# MCU_Module.net
KiCad netlist of a schematic drawn in Altium Designer
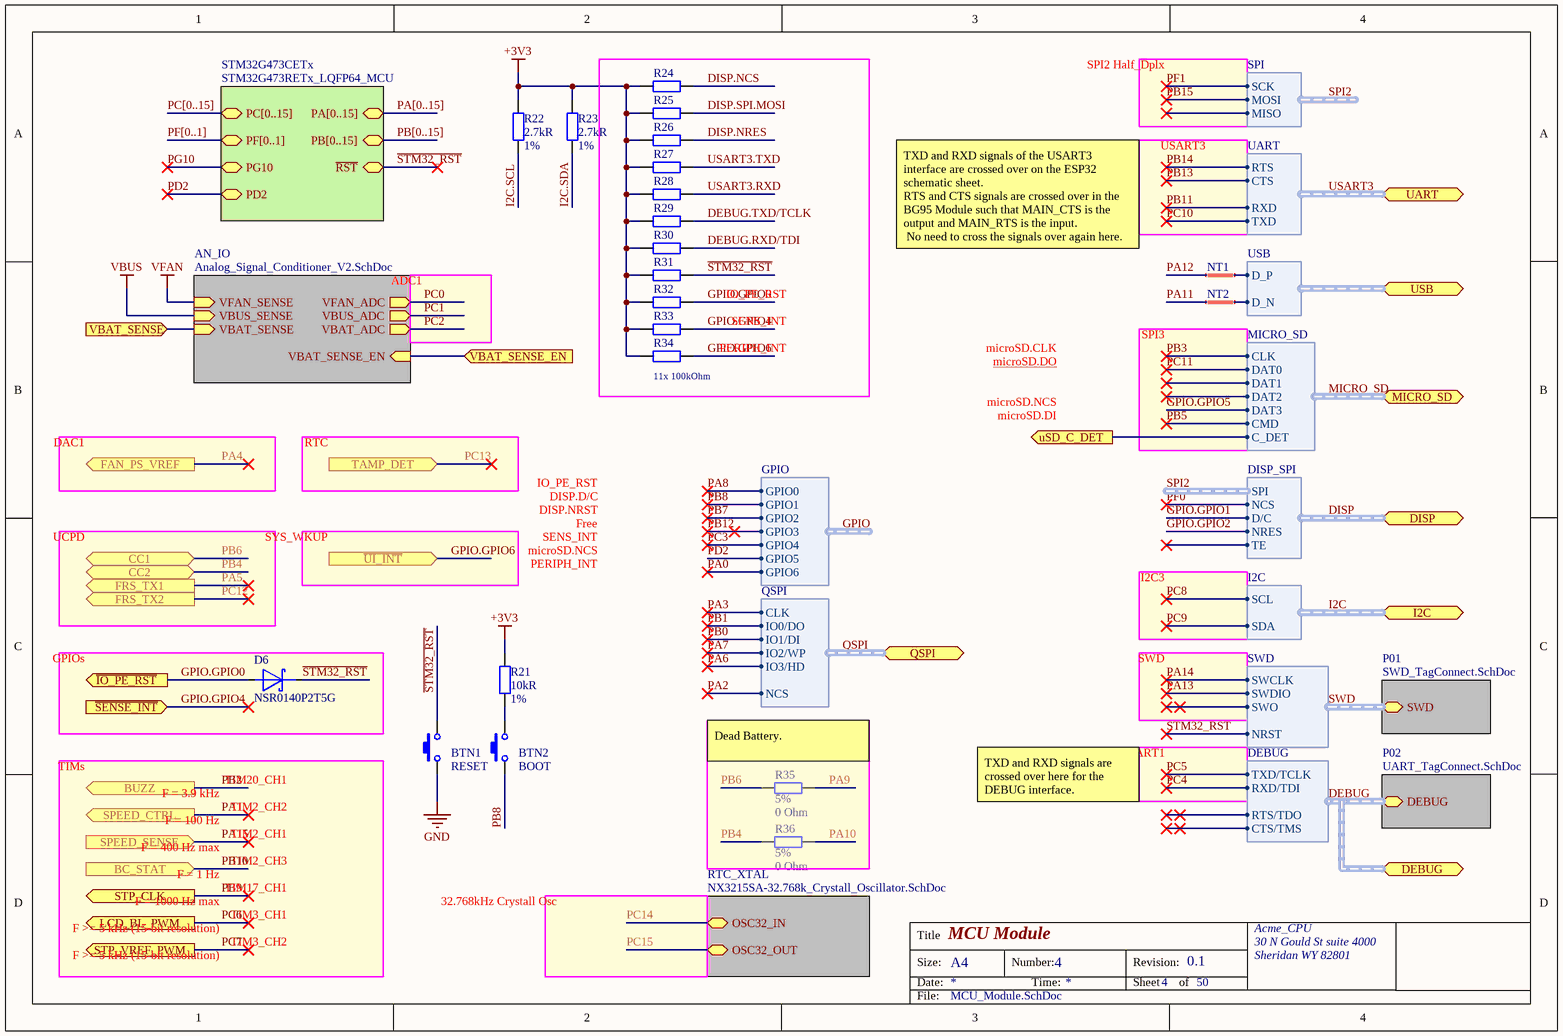
[diagram p0: MCU_Module.SchDoc]

(export (version "E")
  (design (tool "Eeschema 10.0.6"))
  (components
    (comp (ref "BTN1")
      (value "RESET")
      (footprint "SWITCH USLPT2819DT2TR TACTILE TE")
      (description "Tactile Switch SPST-NO Top Actuated Surface Mount")
      (fields
        (field (name "MANUFACTURER") "TE Connectivity")
        (field (name "MANUFACTURER PART NUMBER") "USLPT2819DT2TR")
      )
      (libsource (lib "BLDC_Motor_Driver") (part "TACT ULTRA TB 2.8X1.9X0.6 160GF"))
    )
    (comp (ref "BTN2")
      (value "BOOT")
      (footprint "SWITCH USLPT2819DT2TR TACTILE TE")
      (description "Tactile Switch SPST-NO Top Actuated Surface Mount")
      (fields
        (field (name "MANUFACTURER") "TE Connectivity")
        (field (name "MANUFACTURER PART NUMBER") "USLPT2819DT2TR")
      )
      (libsource (lib "BLDC_Motor_Driver") (part "TACT ULTRA TB 2.8X1.9X0.6 160GF"))
    )
    (comp (ref "D6")
      (value "NSR0140P2T5G")
      (footprint "SODFL100X40-2N")
      (description "Diode Schottky 30V 70mA (DC) Surface Mount SOD-923")
      (fields (field (name "MANUFACTURER") "ON Semiconductor"))
      (libsource (lib "diodes_schottky") (part "DIODE SCHOTTKY 30V 70MA SOD923"))
    )
    (comp (ref "NT1")
      (value "Net Tie")
      (footprint "Net Tie 6x30mil")
      (libsource (lib "BLDC_Motor_Driver") (part "Net Tie Line"))
    )
    (comp (ref "NT2")
      (value "Net Tie")
      (footprint "Net Tie 6x30mil")
      (libsource (lib "BLDC_Motor_Driver") (part "Net Tie Line"))
    )
    (comp (ref "R21")
      (value "RES SMD 10K OHM 1% 1/16W 0402")
      (footprint "R0402")
      (description "10 kOhms ±1% 0.063W, 1/16W Chip Resistor 0402 (1005 Metric) Moisture Resistant Thick Film")
      (fields
        (field (name "MANUFACTURER PART NUMBER") "RC0402FR-0710KP")
        (field (name "MANUFACTURER") "Yageo")
        (field (name "RESISTANCE") "10kR")
        (field (name "TOLERANCE") "1%")
      )
      (libsource (lib "resistors_smd") (part "RES SMD 10K OHM 1% 1/16W 0402"))
    )
    (comp (ref "R22")
      (value "RES SMD 2.7K OHM 1% 1/16W 0402")
      (footprint "R0402")
      (description "2.7 kOhms ±1% 0.063W, 1/16W Chip Resistor 0402 (1005 Metric) Moisture Resistant Thick Film")
      (fields
        (field (name "MANUFACTURER") "Yageo")
        (field (name "MANUFACTURER PART NUMBER") "RC0402FR-072K7L")
        (field (name "RESISTANCE") "2.7kR")
        (field (name "TOLERANCE") "1%")
      )
      (libsource (lib "resistors_smd") (part "RES SMD 2.7K OHM 1% 1/16W 0402"))
    )
    (comp (ref "R23")
      (value "RES SMD 2.7K OHM 1% 1/16W 0402")
      (footprint "R0402")
      (description "2.7 kOhms ±1% 0.063W, 1/16W Chip Resistor 0402 (1005 Metric) Moisture Resistant Thick Film")
      (fields
        (field (name "MANUFACTURER") "Yageo")
        (field (name "MANUFACTURER PART NUMBER") "RC0402FR-072K7L")
        (field (name "RESISTANCE") "2.7kR")
        (field (name "TOLERANCE") "1%")
      )
      (libsource (lib "resistors_smd") (part "RES SMD 2.7K OHM 1% 1/16W 0402"))
    )
    (comp (ref "R24")
      (value "RES SMD 100K OHM 1% 1/16W 0402")
      (footprint "R0402")
      (description "100 kOhms ±1% 0.063W, 1/16W Chip Resistor 0402 (1005 Metric) Moisture Resistant Thick Film")
      (fields
        (field (name "MANUFACTURER") "Yageo")
        (field (name "MANUFACTURER PART NUMBER") "RC0402FR-07100KL")
      )
      (libsource (lib "resistors_smd") (part "RES SMD 100K OHM 1% 1/16W 0402"))
    )
    (comp (ref "R25")
      (value "RES SMD 100K OHM 1% 1/16W 0402")
      (footprint "R0402")
      (description "100 kOhms ±1% 0.063W, 1/16W Chip Resistor 0402 (1005 Metric) Moisture Resistant Thick Film")
      (fields
        (field (name "MANUFACTURER") "Yageo")
        (field (name "MANUFACTURER PART NUMBER") "RC0402FR-07100KL")
      )
      (libsource (lib "resistors_smd") (part "RES SMD 100K OHM 1% 1/16W 0402"))
    )
    (comp (ref "R26")
      (value "RES SMD 100K OHM 1% 1/16W 0402")
      (footprint "R0402")
      (description "100 kOhms ±1% 0.063W, 1/16W Chip Resistor 0402 (1005 Metric) Moisture Resistant Thick Film")
      (fields
        (field (name "MANUFACTURER") "Yageo")
        (field (name "MANUFACTURER PART NUMBER") "RC0402FR-07100KL")
      )
      (libsource (lib "resistors_smd") (part "RES SMD 100K OHM 1% 1/16W 0402"))
    )
    (comp (ref "R27")
      (value "RES SMD 100K OHM 1% 1/16W 0402")
      (footprint "R0402")
      (description "100 kOhms ±1% 0.063W, 1/16W Chip Resistor 0402 (1005 Metric) Moisture Resistant Thick Film")
      (fields
        (field (name "MANUFACTURER") "Yageo")
        (field (name "MANUFACTURER PART NUMBER") "RC0402FR-07100KL")
      )
      (libsource (lib "resistors_smd") (part "RES SMD 100K OHM 1% 1/16W 0402"))
    )
    (comp (ref "R28")
      (value "RES SMD 100K OHM 1% 1/16W 0402")
      (footprint "R0402")
      (description "100 kOhms ±1% 0.063W, 1/16W Chip Resistor 0402 (1005 Metric) Moisture Resistant Thick Film")
      (fields
        (field (name "MANUFACTURER") "Yageo")
        (field (name "MANUFACTURER PART NUMBER") "RC0402FR-07100KL")
      )
      (libsource (lib "resistors_smd") (part "RES SMD 100K OHM 1% 1/16W 0402"))
    )
    (comp (ref "R29")
      (value "RES SMD 100K OHM 1% 1/16W 0402")
      (footprint "R0402")
      (description "100 kOhms ±1% 0.063W, 1/16W Chip Resistor 0402 (1005 Metric) Moisture Resistant Thick Film")
      (fields
        (field (name "MANUFACTURER") "Yageo")
        (field (name "MANUFACTURER PART NUMBER") "RC0402FR-07100KL")
      )
      (libsource (lib "resistors_smd") (part "RES SMD 100K OHM 1% 1/16W 0402"))
    )
    (comp (ref "R30")
      (value "RES SMD 100K OHM 1% 1/16W 0402")
      (footprint "R0402")
      (description "100 kOhms ±1% 0.063W, 1/16W Chip Resistor 0402 (1005 Metric) Moisture Resistant Thick Film")
      (fields
        (field (name "MANUFACTURER") "Yageo")
        (field (name "MANUFACTURER PART NUMBER") "RC0402FR-07100KL")
      )
      (libsource (lib "resistors_smd") (part "RES SMD 100K OHM 1% 1/16W 0402"))
    )
    (comp (ref "R31")
      (value "RES SMD 100K OHM 1% 1/16W 0402")
      (footprint "R0402")
      (description "100 kOhms ±1% 0.063W, 1/16W Chip Resistor 0402 (1005 Metric) Moisture Resistant Thick Film")
      (fields
        (field (name "MANUFACTURER") "Yageo")
        (field (name "MANUFACTURER PART NUMBER") "RC0402FR-07100KL")
      )
      (libsource (lib "resistors_smd") (part "RES SMD 100K OHM 1% 1/16W 0402"))
    )
    (comp (ref "R32")
      (value "RES SMD 100K OHM 1% 1/16W 0402")
      (footprint "R0402")
      (description "100 kOhms ±1% 0.063W, 1/16W Chip Resistor 0402 (1005 Metric) Moisture Resistant Thick Film")
      (fields
        (field (name "MANUFACTURER") "Yageo")
        (field (name "MANUFACTURER PART NUMBER") "RC0402FR-07100KL")
      )
      (libsource (lib "resistors_smd") (part "RES SMD 100K OHM 1% 1/16W 0402"))
    )
    (comp (ref "R33")
      (value "RES SMD 100K OHM 1% 1/16W 0402")
      (footprint "R0402")
      (description "100 kOhms ±1% 0.063W, 1/16W Chip Resistor 0402 (1005 Metric) Moisture Resistant Thick Film")
      (fields
        (field (name "MANUFACTURER") "Yageo")
        (field (name "MANUFACTURER PART NUMBER") "RC0402FR-07100KL")
      )
      (libsource (lib "resistors_smd") (part "RES SMD 100K OHM 1% 1/16W 0402"))
    )
    (comp (ref "R34")
      (value "RES SMD 100K OHM 1% 1/16W 0402")
      (footprint "R0402")
      (description "100 kOhms ±1% 0.063W, 1/16W Chip Resistor 0402 (1005 Metric) Moisture Resistant Thick Film")
      (fields
        (field (name "MANUFACTURER") "Yageo")
        (field (name "MANUFACTURER PART NUMBER") "RC0402FR-07100KL")
      )
      (libsource (lib "resistors_smd") (part "RES SMD 100K OHM 1% 1/16W 0402"))
    )
    (comp (ref "R35")
      (value "RES SMD 0 OHM JUMPER 1/16W 0402")
      (footprint "R0402")
      (description "0 Ohms Jumper 0.063W, 1/16W Chip Resistor 0402 (1005 Metric) Moisture Resistant Thick Film")
      (fields
        (field (name "MANUFACTURER") "Yageo")
        (field (name "MANUFACTURER PART NUMBER") "RC0402JR-070RL")
        (field (name "TOLERANCE") "5%")
        (field (name "RESISTANCE") "0 Ohm")
      )
      (libsource (lib "resistors_smd") (part "RES SMD 0 OHM JUMPER 1/16W 0402"))
    )
    (comp (ref "R36")
      (value "RES SMD 0 OHM JUMPER 1/16W 0402")
      (footprint "R0402")
      (description "0 Ohms Jumper 0.063W, 1/16W Chip Resistor 0402 (1005 Metric) Moisture Resistant Thick Film")
      (fields
        (field (name "MANUFACTURER") "Yageo")
        (field (name "MANUFACTURER PART NUMBER") "RC0402JR-070RL")
        (field (name "TOLERANCE") "5%")
        (field (name "RESISTANCE") "0 Ohm")
      )
      (libsource (lib "resistors_smd") (part "RES SMD 0 OHM JUMPER 1/16W 0402"))
    )
  )
  (nets
    (net (code "12") (name "+3V3") (class "Default")
      (node (ref "R21") (pin "1") (pinfunction "1_1") (pintype "passive"))
      (node (ref "R22") (pin "2") (pinfunction "2_2") (pintype "passive"))
      (node (ref "R23") (pin "2") (pinfunction "2_2") (pintype "passive"))
      (node (ref "R24") (pin "1") (pinfunction "1_1") (pintype "passive"))
      (node (ref "R25") (pin "1") (pinfunction "1_1") (pintype "passive"))
      (node (ref "R26") (pin "1") (pinfunction "1_1") (pintype "passive"))
      (node (ref "R27") (pin "1") (pinfunction "1_1") (pintype "passive"))
      (node (ref "R28") (pin "1") (pinfunction "1_1") (pintype "passive"))
      (node (ref "R29") (pin "1") (pinfunction "1_1") (pintype "passive"))
      (node (ref "R30") (pin "1") (pinfunction "1_1") (pintype "passive"))
      (node (ref "R31") (pin "1") (pinfunction "1_1") (pintype "passive"))
      (node (ref "R32") (pin "1") (pinfunction "1_1") (pintype "passive"))
      (node (ref "R33") (pin "1") (pinfunction "1_1") (pintype "passive"))
      (node (ref "R34") (pin "1") (pinfunction "1_1") (pintype "passive"))
    )
    (net (code "16") (name "/DEBUG.RXD{slash}TDI") (class "Default")
      (node (ref "R30") (pin "2") (pinfunction "2_2") (pintype "passive"))
    )
    (net (code "17") (name "/DEBUG.TXD{slash}TCLK") (class "Default")
      (node (ref "R29") (pin "2") (pinfunction "2_2") (pintype "passive"))
    )
    (net (code "19") (name "/DISP.NCS") (class "Default")
      (node (ref "R24") (pin "2") (pinfunction "2_2") (pintype "passive"))
    )
    (net (code "20") (name "/DISP.NRES") (class "Default")
      (node (ref "R26") (pin "2") (pinfunction "2_2") (pintype "passive"))
    )
    (net (code "21") (name "/DISP.SPI.MOSI") (class "Default")
      (node (ref "R25") (pin "2") (pinfunction "2_2") (pintype "passive"))
    )
    (net (code "22") (name "/D_N") (class "Default") (node (ref "NT2") (pin "2") (pintype "passive")))
    (net (code "23") (name "/D_P") (class "Default") (node (ref "NT1") (pin "2") (pintype "passive")))
    (net (code "24") (name "/GPIO.GPIO0") (class "Default")
      (node (ref "D6") (pin "2") (pinfunction "A_2") (pintype "passive"))
      (node (ref "R32") (pin "2") (pinfunction "2_2") (pintype "passive"))
    )
    (net (code "27") (name "/GPIO.GPIO4") (class "Default")
      (node (ref "R33") (pin "2") (pinfunction "2_2") (pintype "passive"))
    )
    (net (code "29") (name "/GPIO.GPIO6") (class "Default")
      (node (ref "R34") (pin "2") (pinfunction "2_2") (pintype "passive"))
    )
    (net (code "31") (name "/I2C.SCL") (class "Default")
      (node (ref "R22") (pin "1") (pinfunction "1_1") (pintype "passive"))
    )
    (net (code "32") (name "/I2C.SDA") (class "Default")
      (node (ref "R23") (pin "1") (pinfunction "1_1") (pintype "passive"))
    )
    (net (code "45") (name "/PA9") (class "Default")
      (node (ref "R35") (pin "2") (pinfunction "2_2") (pintype "passive"))
    )
    (net (code "46") (name "/PA10") (class "Default")
      (node (ref "R36") (pin "2") (pinfunction "2_2") (pintype "passive"))
    )
    (net (code "47") (name "/PA11") (class "Default") (node (ref "NT2") (pin "1") (pintype "passive")))
    (net (code "48") (name "/PA12") (class "Default") (node (ref "NT1") (pin "1") (pintype "passive")))
    (net (code "57") (name "/PB4") (class "Default")
      (node (ref "R36") (pin "1") (pinfunction "1_1") (pintype "passive"))
    )
    (net (code "59") (name "/PB6") (class "Default")
      (node (ref "R35") (pin "1") (pinfunction "1_1") (pintype "passive"))
    )
    (net (code "61") (name "/PB8") (class "Default")
      (node (ref "BTN2") (pin "2") (pinfunction "2_2") (pintype "passive+no_connect"))
    )
    (net (code "96") (name "/STM32_RST") (class "Default")
      (node (ref "BTN1") (pin "1") (pinfunction "1_1") (pintype "passive"))
      (node (ref "D6") (pin "1") (pinfunction "K_1") (pintype "passive"))
      (node (ref "R31") (pin "2") (pinfunction "2_2") (pintype "passive"))
    )
    (net (code "100") (name "/USART3.RXD") (class "Default")
      (node (ref "R28") (pin "2") (pinfunction "2_2") (pintype "passive"))
    )
    (net (code "101") (name "/USART3.TXD") (class "Default")
      (node (ref "R27") (pin "2") (pinfunction "2_2") (pintype "passive"))
    )
    (net (code "108") (name "GND") (class "Default")
      (node (ref "BTN1") (pin "2") (pinfunction "2_2") (pintype "passive"))
    )
    (net (code "109") (name "Net-(BTN2-Pad1)") (class "Default")
      (node (ref "BTN2") (pin "1") (pinfunction "1_1") (pintype "passive"))
      (node (ref "R21") (pin "2") (pinfunction "2_2") (pintype "passive"))
    )
  )
)
